# Boost_6V.net
KiCad netlist of a schematic drawn in Altium Designer
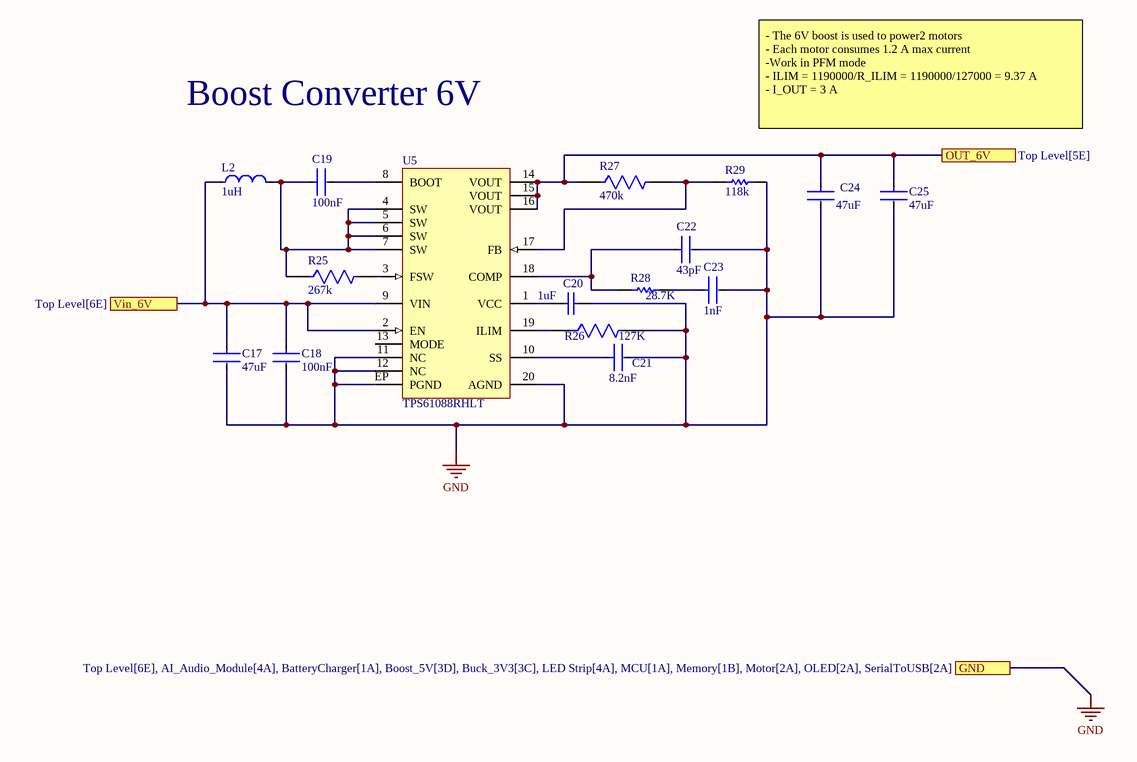
[diagram p0: Boost_6V.SchDoc]

(export (version "E")
  (design (tool "Eeschema 10.0.6"))
  (components
    (comp (ref "C17")
      (value "47uF")
      (footprint "FP-C0805C476M9PACTU-MFG")
      (description "CAP CER 47UF 6.3V X5R 0805")
      (fields (field (name "VOLTAGE") "6.3V") (field (name "TOLERANCE") "20%"))
      (libsource (lib "Altium Content Vault") (part "11868f565c42a9108669ba33697ecf6"))
    )
    (comp (ref "C18")
      (value "100nF")
      (footprint "FP-CC0603-DA-MFG")
      (description "CAP CER 0.1UF 16V X7R 0603")
      (fields
        (field (name "OCTOPART") "https://octopart.com/cc0603krx7r7bb104-yageo-192941")
        (field (name "TOLERANCE") "0.1")
      )
      (libsource (lib "Altium Content Vault") (part "11868f565c42a9108669ba33697ecf6"))
    )
    (comp (ref "C19")
      (value "100nF")
      (footprint "FP-CGA3E-0_3-0_1-IPC_A")
      (description "Cap Ceramic 100nF 50V X7R 10% Pad SMD 0603 +125°C Automotive T/R")
      (fields (field (name "TOLERANCE") "10%") (field (name "VOLTAGE") "50V"))
      (libsource (lib "Altium Content Vault") (part "b4654b650e69147ec39a6b967a45e02"))
    )
    (comp (ref "C20")
      (value "1uF")
      (footprint "CAPC1608X87X35LL15T15")
      (fields (field (name "PART NUMBER") "C0603C105K3RACTU") (field (name "MANUFACTURER") "Kemet"))
      (libsource (lib "Altium Content Vault") (part "CAP"))
    )
    (comp (ref "C21")
      (value "8.2nF")
      (footprint "FP-C0805C-DN-MFG")
      (description "CAP CER 8200PF 200V C0G/NP0 0805")
      (fields
        (field (name "TOLERANCE") "0.05")
        (field (name "MANUFACTURER PART NUMBER") "C0805C822J2GACAUTO")
      )
      (libsource (lib "Altium Content Vault") (part "b4654b650e69147ec39a6b967a45e02"))
    )
    (comp (ref "C22")
      (value "43pF")
      (footprint "FP-C0603C-CF-MFG")
      (description "CAP CER 43PF 50V 5% NP0 0603")
      (fields
        (field (name "TOLERANCE") "0.05")
        (field (name "OCTOPART") "https://octopart.com/c0603c430j5gactu-kemet-9138600")
      )
      (libsource (lib "Altium Content Vault") (part "b4654b650e69147ec39a6b967a45e02"))
    )
    (comp (ref "C23")
      (value "1nF")
      (footprint "FP-0603-L_1_6_0_15-W_0_81-IPC_A")
      (description "General Purpose Ceramic Capacitor, 0603, 1nF, 10%, X7R, 15%, 50V")
      (fields (field (name "VOLTAGE") "50V") (field (name "TOLERANCE") "10%"))
      (libsource (lib "Altium Content Vault") (part "02cd4be3c70576c341d710602a673aa"))
    )
    (comp (ref "C24")
      (value "47uF")
      (footprint "FP-C0805C476M9PACTU-MFG")
      (description "CAP CER 47UF 6.3V X5R 0805")
      (fields (field (name "VOLTAGE") "6.3V") (field (name "TOLERANCE") "20%"))
      (libsource (lib "Altium Content Vault") (part "11868f565c42a9108669ba33697ecf6"))
    )
    (comp (ref "C25")
      (value "47uF")
      (footprint "FP-C0805C476M9PACTU-MFG")
      (description "CAP CER 47UF 6.3V X5R 0805")
      (fields (field (name "VOLTAGE") "6.3V") (field (name "TOLERANCE") "20%"))
      (libsource (lib "Altium Content Vault") (part "11868f565c42a9108669ba33697ecf6"))
    )
    (comp (ref "L2")
      (value "1uH")
      (footprint "FP-LQW21HN_00-MFG")
      (description "FIXED IND 1UH 115MA 2.86 OHM SMD")
      (fields (field (name "TOLERANCE") "5%"))
      (libsource (lib "Altium Content Vault") (part "725321dda6339637d4d059423bc1c3c"))
    )
    (comp (ref "R25")
      (value "267k")
      (footprint "FP-RP732A-MFG")
      (fields (field (name "TOLERANCE") "0.1%"))
      (libsource (lib "Altium Content Vault") (part "1029c3af85768c4190bb7ad29bc67b5"))
    )
    (comp (ref "R26")
      (value "127K")
      (footprint "FP-CRCW0805-e3-MFG")
      (description "RES Thick Film, 127kΩ, 1%, 0.125W, 100ppm/°C, 0805")
      (fields (field (name "TOLERANCE") "1%"))
      (libsource (lib "Altium Content Vault") (part "1029c3af85768c4190bb7ad29bc67b5"))
    )
    (comp (ref "R27")
      (value "470k")
      (footprint "FP-CRGCQ0805-IPC_C")
      (description "CRGCQ0805 470KΩ 0.125W ±100ppm/°C 5% 150V")
      (fields (field (name "TOLERANCE") "0.05") (field (name "MANUFACTURER PART NUMBER") "CRGCQ0805J470K"))
      (libsource (lib "Altium Content Vault") (part "1029c3af85768c4190bb7ad29bc67b5"))
    )
    (comp (ref "R28")
      (value "28.7K")
      (footprint "RESC1609X50X30NL10T20")
      (fields (field (name "MANUFACTURER") "Vishay Dale") (field (name "PART NUMBER") "CRCW060328K7FKEA"))
      (libsource (lib "Altium Content Vault") (part "RES"))
    )
    (comp (ref "R29")
      (value "118k")
      (footprint "RESC2013X70X40NL20T20")
      (fields (field (name "PART NUMBER") "ERJ-6ENF1183V") (field (name "MANUFACTURER") "Panasonic"))
      (libsource (lib "Altium Content Vault") (part "RES"))
    )
    (comp (ref "U5")
      (value "TPS61088RHLT")
      (footprint "FP-RHL0020A-MFG")
      (description "Switching Regulator, Current-mode, 13A, 2200kHz Switching Freq-Max, PQCC20")
      (libsource (lib "University of Pennsylvania (ESE)") (part "866d791168d43c93e8e886550da2fd8"))
    )
  )
  (nets
    (net (code "1") (name "/OUT_6V") (class "Default")
      (node (ref "C24") (pin "1") (pinfunction "1_1") (pintype "passive"))
      (node (ref "C25") (pin "1") (pinfunction "1_1") (pintype "passive"))
      (node (ref "R27") (pin "1") (pinfunction "1_1") (pintype "passive"))
      (node (ref "U5") (pin "14") (pinfunction "VOUT_14") (pintype "power_in"))
      (node (ref "U5") (pin "15") (pinfunction "VOUT_15") (pintype "power_in"))
      (node (ref "U5") (pin "16") (pinfunction "VOUT_16") (pintype "power_in"))
    )
    (net (code "2") (name "/Vin_6V") (class "Default")
      (node (ref "C17") (pin "1") (pinfunction "1_1") (pintype "passive"))
      (node (ref "C18") (pin "1") (pinfunction "1_1") (pintype "passive"))
      (node (ref "L2") (pin "1") (pinfunction "1_1") (pintype "passive"))
      (node (ref "U5") (pin "2") (pinfunction "EN_2") (pintype "input"))
      (node (ref "U5") (pin "9") (pinfunction "VIN_9") (pintype "power_in"))
    )
    (net (code "3") (name "GND") (class "Default")
      (node (ref "C17") (pin "2") (pinfunction "2_2") (pintype "passive"))
      (node (ref "C18") (pin "2") (pinfunction "2_2") (pintype "passive"))
      (node (ref "C20") (pin "2") (pinfunction "2_2") (pintype "passive"))
      (node (ref "C21") (pin "2") (pinfunction "2_2") (pintype "passive"))
      (node (ref "C22") (pin "2") (pinfunction "2_2") (pintype "passive"))
      (node (ref "C23") (pin "2") (pinfunction "2_2") (pintype "passive"))
      (node (ref "C24") (pin "2") (pinfunction "2_2") (pintype "passive"))
      (node (ref "C25") (pin "2") (pinfunction "2_2") (pintype "passive"))
      (node (ref "R26") (pin "2") (pinfunction "2_2") (pintype "passive"))
      (node (ref "R29") (pin "2") (pinfunction "2_2") (pintype "passive"))
      (node (ref "U5") (pin "11") (pinfunction "NC_11") (pintype "passive"))
      (node (ref "U5") (pin "12") (pinfunction "NC_12") (pintype "passive"))
      (node (ref "U5") (pin "20") (pinfunction "AGND_20") (pintype "power_in"))
      (node (ref "U5") (pin "EP") (pinfunction "PGND_EP") (pintype "power_in"))
    )
    (net (code "4") (name "Net-(C19-Pad1)") (class "Default")
      (node (ref "C19") (pin "1") (pinfunction "1_1") (pintype "passive"))
      (node (ref "L2") (pin "2") (pinfunction "2_2") (pintype "passive"))
      (node (ref "R25") (pin "1") (pinfunction "1_1") (pintype "passive"))
      (node (ref "U5") (pin "4") (pinfunction "SW_4") (pintype "power_in"))
      (node (ref "U5") (pin "5") (pinfunction "SW_5") (pintype "power_in"))
      (node (ref "U5") (pin "6") (pinfunction "SW_6") (pintype "power_in"))
      (node (ref "U5") (pin "7") (pinfunction "SW_7") (pintype "power_in"))
    )
    (net (code "5") (name "Net-(C23-Pad1)") (class "Default")
      (node (ref "C23") (pin "1") (pinfunction "1_1") (pintype "passive"))
      (node (ref "R28") (pin "2") (pinfunction "2_2") (pintype "passive"))
    )
    (net (code "6") (name "Net-(U5-BOOT)") (class "Default")
      (node (ref "C19") (pin "2") (pinfunction "2_2") (pintype "passive"))
      (node (ref "U5") (pin "8") (pinfunction "BOOT_8") (pintype "power_in"))
    )
    (net (code "7") (name "Net-(U5-COMP)") (class "Default")
      (node (ref "C22") (pin "1") (pinfunction "1_1") (pintype "passive"))
      (node (ref "R28") (pin "1") (pinfunction "1_1") (pintype "passive"))
      (node (ref "U5") (pin "18") (pinfunction "COMP_18") (pintype "passive"))
    )
    (net (code "8") (name "Net-(U5-FB)") (class "Default")
      (node (ref "R27") (pin "2") (pinfunction "2_2") (pintype "passive"))
      (node (ref "R29") (pin "1") (pinfunction "1_1") (pintype "passive"))
      (node (ref "U5") (pin "17") (pinfunction "FB_17") (pintype "input"))
    )
    (net (code "9") (name "Net-(U5-FSW)") (class "Default")
      (node (ref "R25") (pin "2") (pinfunction "2_2") (pintype "passive"))
      (node (ref "U5") (pin "3") (pinfunction "FSW_3") (pintype "input"))
    )
    (net (code "10") (name "Net-(U5-ILIM)") (class "Default")
      (node (ref "R26") (pin "1") (pinfunction "1_1") (pintype "passive"))
      (node (ref "U5") (pin "19") (pinfunction "ILIM_19") (pintype "passive"))
    )
    (net (code "11") (name "Net-(U5-SS)") (class "Default")
      (node (ref "C21") (pin "1") (pinfunction "1_1") (pintype "passive"))
      (node (ref "U5") (pin "10") (pinfunction "SS_10") (pintype "passive"))
    )
    (net (code "12") (name "Net-(U5-VCC)") (class "Default")
      (node (ref "C20") (pin "1") (pinfunction "1_1") (pintype "passive"))
      (node (ref "U5") (pin "1") (pinfunction "VCC_1") (pintype "power_in"))
    )
    (net (code "13") (name "unconnected-(U5-MODE-Pad13)") (class "Default")
      (node (ref "U5") (pin "13") (pinfunction "MODE_13") (pintype "passive"))
    )
  )
)
